# Power_Regulation_and_Protection.net
KiCad netlist of a schematic drawn in Altium Designer
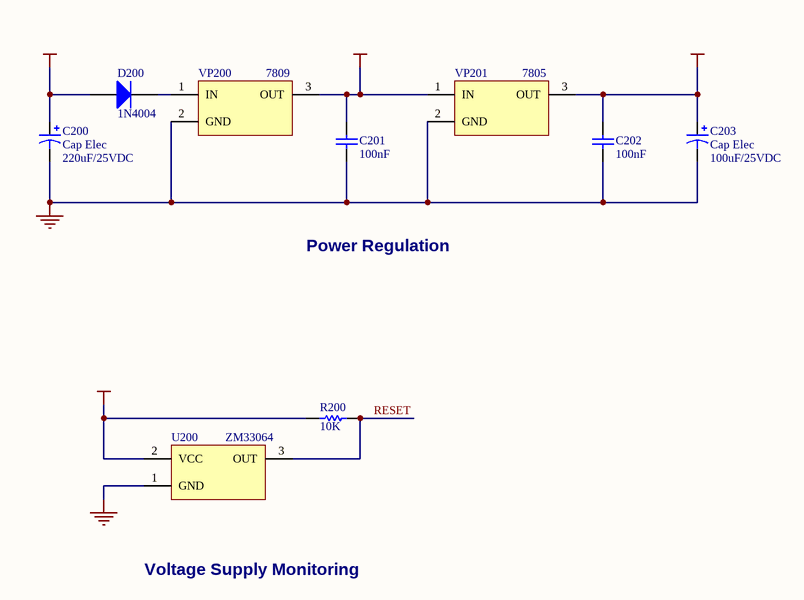
[diagram p0: Power Regulation and Protection.SCHDOC]

(export (version "E")
  (design (tool "Eeschema 10.0.6"))
  (components
    (comp (ref "C200")
      (value "Cap Elec")
      (footprint "CAPR5-4X5")
      (description "Polarized Capacitor (Axial)")
      (fields (field (name "ALTIUM_VALUE") "220uF/25VDC") (field (name "PUBLISHER") "Altium Limited"))
      (libsource (lib "Miscellaneous Devices") (part "Cap Pol2"))
    )
    (comp (ref "C201")
      (value "100nF")
      (footprint "BCY-W2/D3.1")
      (description "Capacitor")
      (fields (field (name "PUBLISHER") "Altium Limited"))
      (libsource (lib "Miscellaneous Devices") (part "Cap"))
    )
    (comp (ref "C202")
      (value "100nF")
      (footprint "BCY-W2/D3.1")
      (description "Capacitor")
      (fields (field (name "PUBLISHER") "Altium Limited"))
      (libsource (lib "Miscellaneous Devices") (part "Cap"))
    )
    (comp (ref "C203")
      (value "Cap Elec")
      (footprint "CAPR5-4X5")
      (description "Polarized Capacitor (Axial)")
      (fields (field (name "ALTIUM_VALUE") "100uF/25VDC") (field (name "PUBLISHER") "Altium Limited"))
      (libsource (lib "Miscellaneous Devices") (part "Cap Pol2"))
    )
    (comp (ref "D200")
      (value "1N4004")
      (footprint "DIO10.46-5.3x2.8")
      (description "1 Amp General Purpose Rectifier")
      (fields (field (name "PUBLISHER") "Altium Limited"))
      (libsource (lib "Miscellaneous Devices") (part "Diode 1N4004"))
    )
    (comp (ref "R200")
      (value "10K")
      (footprint "AXIAL-0.3")
      (description "Resistor")
      (fields (field (name "PUBLISHER") "Altium Limited"))
      (libsource (lib "Miscellaneous Devices") (part "Res1"))
    )
    (comp (ref "U200")
      (value "ZM33064")
      (footprint "BCY-W3")
      (description "Generic 5V Supply Voltage Monitor")
      (libsource (lib "Schematic Library") (part "ZM33064"))
    )
    (comp (ref "VP200")
      (value "7809")
      (footprint "PIN3")
      (description "Generic 9V Voltage Regulator")
      (libsource (lib "Schematic Library") (part "7809"))
    )
    (comp (ref "VP201")
      (value "7805")
      (footprint "PIN3")
      (description "Generic 6V Voltage Regulator")
      (libsource (lib "Schematic Library") (part "7805"))
    )
  )
  (nets
    (net (code "1") (name "/RESET") (class "Default")
      (node (ref "R200") (pin "1") (pinfunction "1_1") (pintype "passive"))
      (node (ref "U200") (pin "3") (pinfunction "OUT_3") (pintype "passive"))
    )
    (net (code "2") (name "5V") (class "Default")
      (node (ref "C202") (pin "2") (pinfunction "2_2") (pintype "passive"))
      (node (ref "C203") (pin "1") (pinfunction "1_1") (pintype "passive"))
      (node (ref "R200") (pin "2") (pinfunction "2_2") (pintype "passive"))
      (node (ref "U200") (pin "2") (pinfunction "VCC_2") (pintype "passive"))
      (node (ref "VP201") (pin "3") (pinfunction "OUT_3") (pintype "passive"))
    )
    (net (code "3") (name "9V") (class "Default")
      (node (ref "C201") (pin "2") (pinfunction "2_2") (pintype "passive"))
      (node (ref "VP200") (pin "3") (pinfunction "OUT_3") (pintype "passive"))
      (node (ref "VP201") (pin "1") (pinfunction "IN_1") (pintype "passive"))
    )
    (net (code "4") (name "GND") (class "Default")
      (node (ref "C200") (pin "2") (pinfunction "2_2") (pintype "passive"))
      (node (ref "C201") (pin "1") (pinfunction "1_1") (pintype "passive"))
      (node (ref "C202") (pin "1") (pinfunction "1_1") (pintype "passive"))
      (node (ref "C203") (pin "2") (pinfunction "2_2") (pintype "passive"))
      (node (ref "U200") (pin "1") (pinfunction "GND_1") (pintype "passive"))
      (node (ref "VP200") (pin "2") (pinfunction "GND_2") (pintype "passive"))
      (node (ref "VP201") (pin "2") (pinfunction "GND_2") (pintype "passive"))
    )
    (net (code "5") (name "Net-(D200-K)") (class "Default")
      (node (ref "D200") (pin "2") (pinfunction "K_2") (pintype "passive"))
      (node (ref "VP200") (pin "1") (pinfunction "IN_1") (pintype "passive"))
    )
    (net (code "6") (name "VBat") (class "Default")
      (node (ref "C200") (pin "1") (pinfunction "1_1") (pintype "passive"))
      (node (ref "D200") (pin "1") (pinfunction "A_1") (pintype "passive"))
    )
  )
)
